# Adafruit_HUZZAH_ESP8266_Basic_Breakout.net
KiCad netlist of a schematic drawn in EAGLE
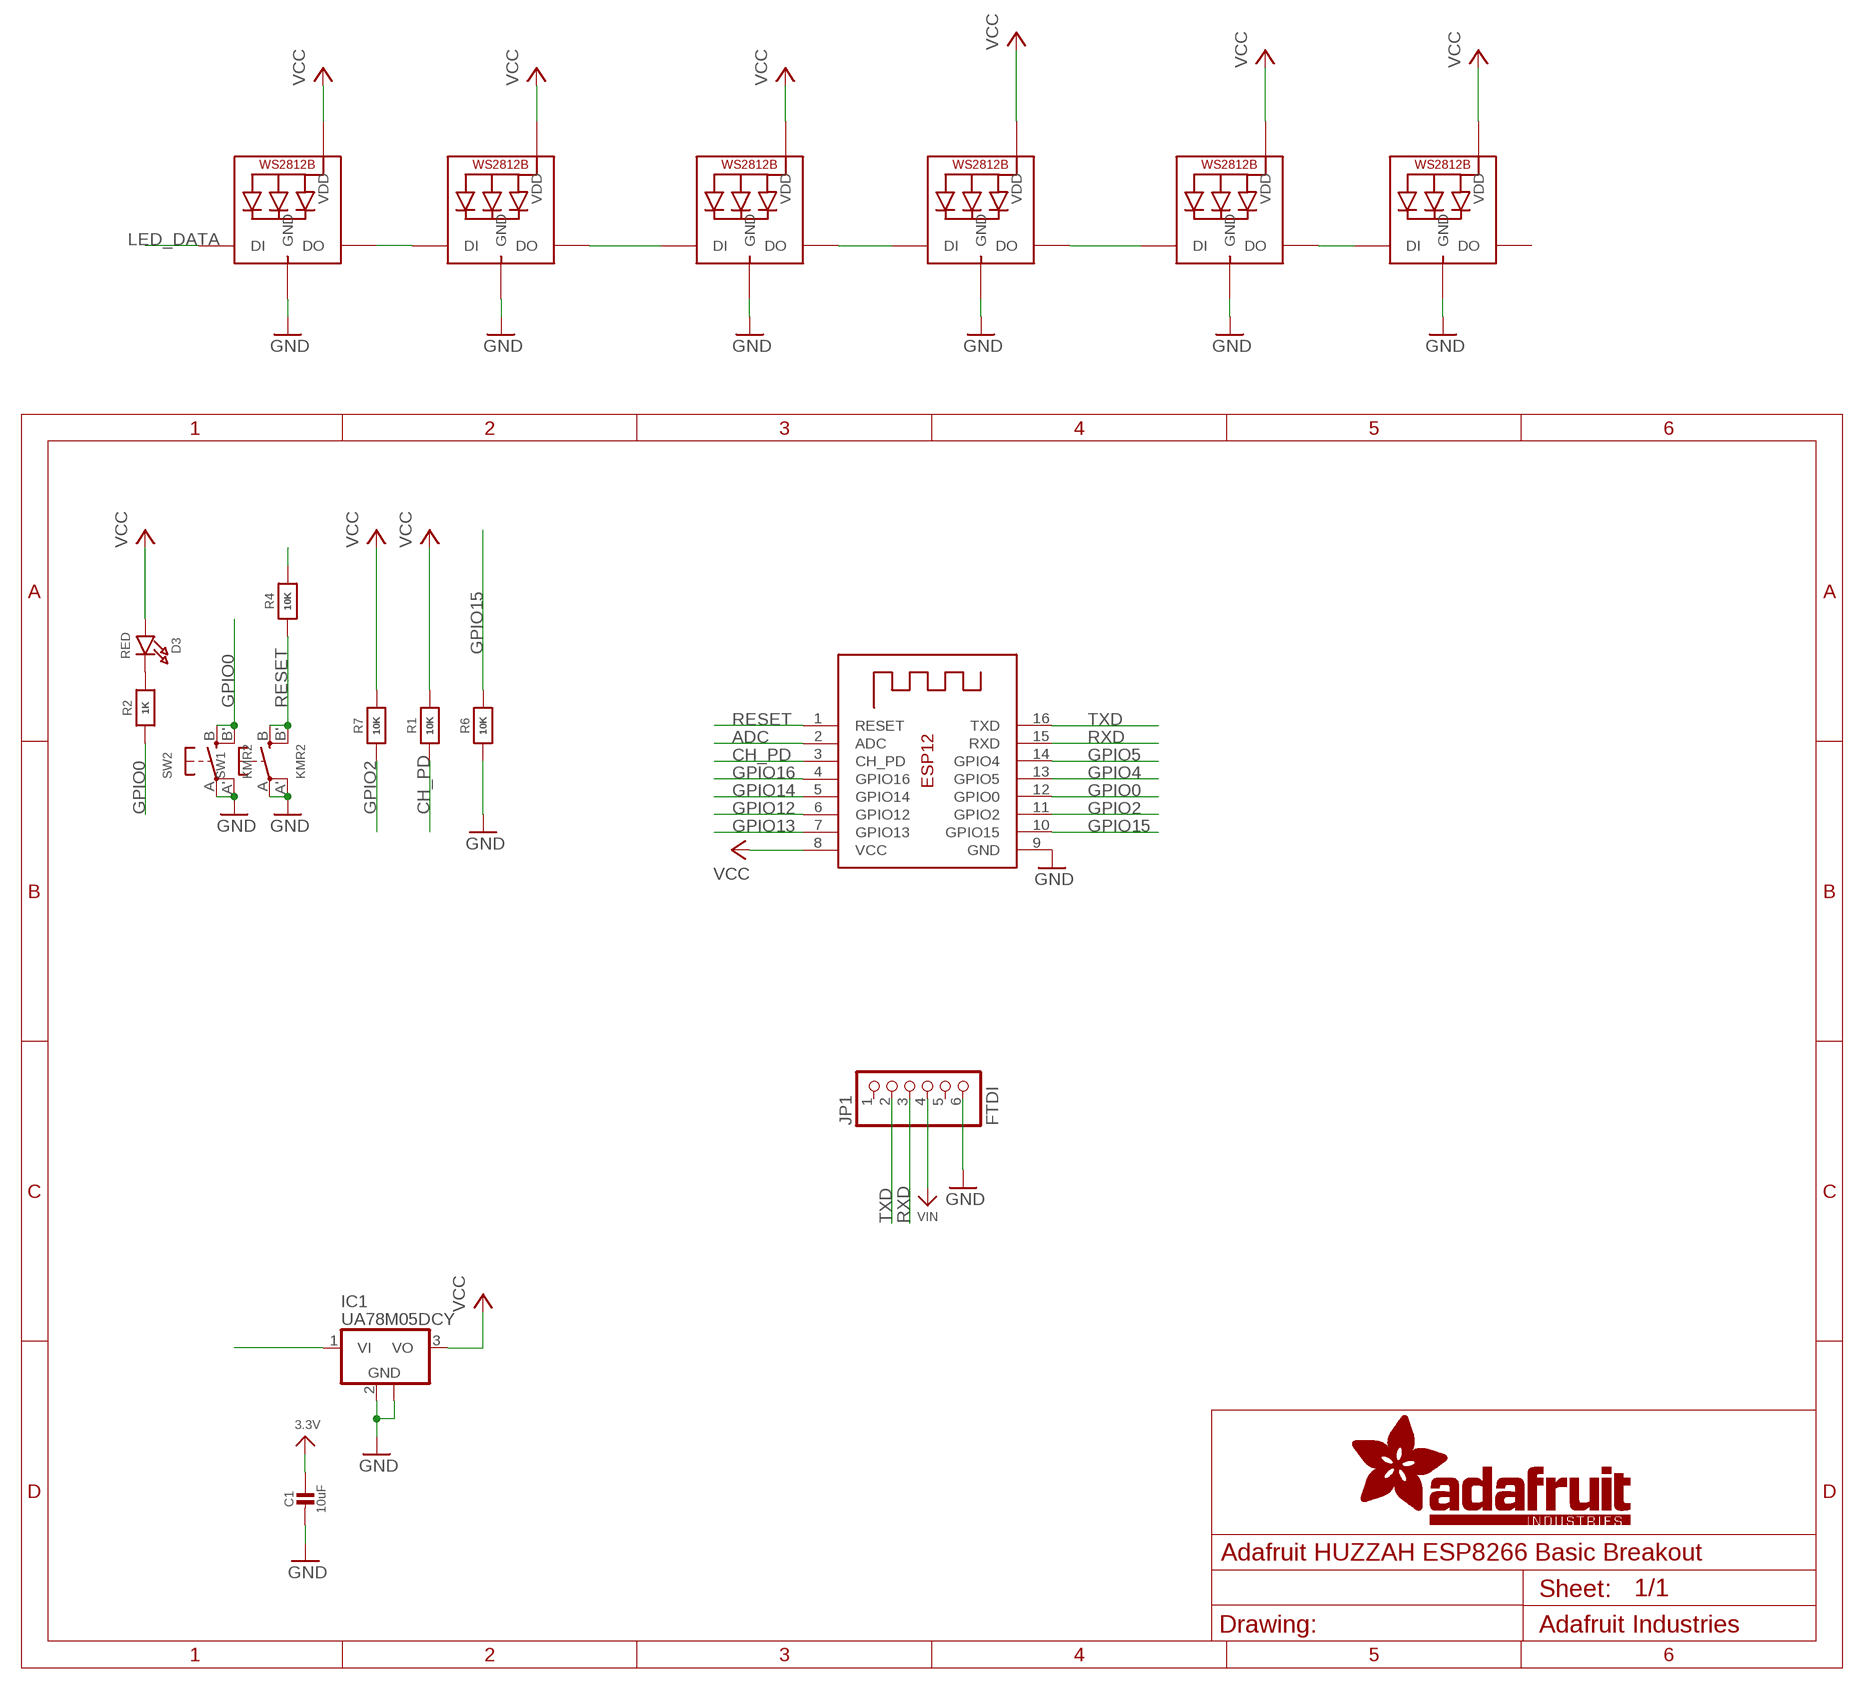
[diagram p0: schematic, sheet 1]

(export (version "E")
  (design (tool "Eeschema 10.0.6"))
  (components
    (comp (ref "C1")
      (value "10uF")
      (footprint "eagle-import:0805-NO")
      (libsource (lib "eagle-import") (part "CAP_CERAMIC0805-NOOUTLINE"))
    )
    (comp (ref "D3")
      (value "RED")
      (footprint "eagle-import:CHIPLED_0805_NOOUTLINE")
      (libsource (lib "eagle-import") (part "LED0805_NOOUTLINE"))
    )
    (comp (ref "IC1")
      (value "UA78M05DCY")
      (footprint "eagle-import:SOT223")
      (libsource (lib "eagle-import") (part "UA78MDCY05"))
    )
    (comp (ref "JP1")
      (value "FTDI")
      (footprint "eagle-import:1X06_ROUND_70")
      (libsource (lib "eagle-import") (part "HEADER-1X670MIL"))
    )
    (comp (ref "LED1")
      (value "WS2812B5050")
      (footprint "eagle-import:WS2812B")
      (libsource (lib "eagle-import") (part "WS2812B5050"))
    )
    (comp (ref "LED2")
      (value "WS2812B5050")
      (footprint "eagle-import:WS2812B")
      (libsource (lib "eagle-import") (part "WS2812B5050"))
    )
    (comp (ref "LED3")
      (value "WS2812B5050")
      (footprint "eagle-import:WS2812B")
      (libsource (lib "eagle-import") (part "WS2812B5050"))
    )
    (comp (ref "LED4")
      (value "WS2812B5050")
      (footprint "eagle-import:WS2812B")
      (libsource (lib "eagle-import") (part "WS2812B5050"))
    )
    (comp (ref "LED5")
      (value "WS2812B5050")
      (footprint "eagle-import:WS2812B")
      (libsource (lib "eagle-import") (part "WS2812B5050"))
    )
    (comp (ref "LED6")
      (value "WS2812B5050")
      (footprint "eagle-import:WS2812B")
      (libsource (lib "eagle-import") (part "WS2812B5050"))
    )
    (comp (ref "R1")
      (value "10K")
      (footprint "eagle-import:0805-NO")
      (libsource (lib "eagle-import") (part "RESISTOR0805_NOOUTLINE"))
    )
    (comp (ref "R2")
      (value "1K")
      (footprint "eagle-import:0805-NO")
      (libsource (lib "eagle-import") (part "RESISTOR0805_NOOUTLINE"))
    )
    (comp (ref "R4")
      (value "10K")
      (footprint "eagle-import:0805-NO")
      (libsource (lib "eagle-import") (part "RESISTOR0805_NOOUTLINE"))
    )
    (comp (ref "R6")
      (value "10K")
      (footprint "eagle-import:0805-NO")
      (libsource (lib "eagle-import") (part "RESISTOR0805_NOOUTLINE"))
    )
    (comp (ref "R7")
      (value "10K")
      (footprint "eagle-import:0805-NO")
      (libsource (lib "eagle-import") (part "RESISTOR0805_NOOUTLINE"))
    )
    (comp (ref "SW1")
      (value "KMR2")
      (footprint "eagle-import:BTN_KMR2_4.6X2.8")
      (libsource (lib "eagle-import") (part "SWITCH_TACT_SMT4.6X2.8"))
    )
    (comp (ref "SW2")
      (value "KMR2")
      (footprint "eagle-import:BTN_KMR2_4.6X2.8")
      (libsource (lib "eagle-import") (part "SWITCH_TACT_SMT4.6X2.8"))
    )
    (comp (ref "X1")
      (value "ESP-12")
      (footprint "eagle-import:ESP-12")
      (libsource (lib "eagle-import") (part "ESP-12"))
    )
  )
  (nets
    (net (code "1") (name "/ADC") (class "Default")
      (node (ref "X1") (pin "2") (pinfunction "ADC_2") (pintype "passive"))
    )
    (net (code "2") (name "/CH_PD") (class "Default")
      (node (ref "R1") (pin "1") (pinfunction "1_1") (pintype "passive"))
      (node (ref "X1") (pin "3") (pinfunction "CH_PD_3") (pintype "input"))
    )
    (net (code "3") (name "/GPIO0") (class "Default")
      (node (ref "R2") (pin "1") (pinfunction "1_1") (pintype "passive"))
      (node (ref "SW2") (pin "B") (pinfunction "S_B") (pintype "passive"))
      (node (ref "SW2") (pin "B'") (pinfunction "S1_B'") (pintype "passive"))
      (node (ref "X1") (pin "12") (pinfunction "GPIO0_12") (pintype "bidirectional"))
    )
    (net (code "4") (name "/GPIO2") (class "Default")
      (node (ref "R7") (pin "1") (pinfunction "1_1") (pintype "passive"))
      (node (ref "X1") (pin "11") (pinfunction "GPIO2_11") (pintype "bidirectional"))
    )
    (net (code "5") (name "/GPIO4") (class "Default")
      (node (ref "X1") (pin "13") (pinfunction "GPIO5_13") (pintype "bidirectional"))
    )
    (net (code "6") (name "/GPIO5") (class "Default")
      (node (ref "X1") (pin "14") (pinfunction "GPIO4_14") (pintype "bidirectional"))
    )
    (net (code "7") (name "/GPIO12") (class "Default")
      (node (ref "X1") (pin "6") (pinfunction "GPIO12_6") (pintype "bidirectional"))
    )
    (net (code "8") (name "/GPIO13") (class "Default")
      (node (ref "X1") (pin "7") (pinfunction "GPIO13_7") (pintype "bidirectional"))
    )
    (net (code "9") (name "/GPIO14") (class "Default")
      (node (ref "X1") (pin "5") (pinfunction "GPIO14_5") (pintype "bidirectional"))
    )
    (net (code "10") (name "/GPIO15") (class "Default")
      (node (ref "R6") (pin "2") (pinfunction "2_2") (pintype "passive"))
      (node (ref "X1") (pin "10") (pinfunction "GPIO15_10") (pintype "bidirectional"))
    )
    (net (code "11") (name "/GPIO16") (class "Default")
      (node (ref "X1") (pin "4") (pinfunction "GPIO16_4") (pintype "bidirectional"))
    )
    (net (code "12") (name "/LED_DATA") (class "Default")
      (node (ref "LED1") (pin "4-DIN") (pinfunction "DI_4-DIN") (pintype "input"))
    )
    (net (code "13") (name "/RESET") (class "Default")
      (node (ref "R4") (pin "1") (pinfunction "1_1") (pintype "passive"))
      (node (ref "SW1") (pin "B") (pinfunction "S_B") (pintype "passive"))
      (node (ref "SW1") (pin "B'") (pinfunction "S1_B'") (pintype "passive"))
      (node (ref "X1") (pin "1") (pinfunction "RESET_1") (pintype "input"))
    )
    (net (code "14") (name "/RXD") (class "Default")
      (node (ref "JP1") (pin "3") (pinfunction "3_3") (pintype "passive"))
      (node (ref "X1") (pin "15") (pinfunction "RXD_15") (pintype "input"))
    )
    (net (code "15") (name "/TXD") (class "Default")
      (node (ref "JP1") (pin "2") (pinfunction "2_2") (pintype "passive"))
      (node (ref "X1") (pin "16") (pinfunction "TXD_16") (pintype "output"))
    )
    (net (code "16") (name "3.3V") (class "Default")
      (node (ref "C1") (pin "1") (pinfunction "1_1") (pintype "passive"))
    )
    (net (code "17") (name "GND") (class "Default")
      (node (ref "C1") (pin "2") (pinfunction "2_2") (pintype "passive"))
      (node (ref "IC1") (pin "2") (pinfunction "GND_2") (pintype "passive"))
      (node (ref "IC1") (pin "4") (pinfunction "GND_4") (pintype "passive"))
      (node (ref "JP1") (pin "6") (pinfunction "6_6") (pintype "passive"))
      (node (ref "LED1") (pin "3-GND") (pinfunction "GND_3-GND") (pintype "power_in"))
      (node (ref "LED2") (pin "3-GND") (pinfunction "GND_3-GND") (pintype "power_in"))
      (node (ref "LED3") (pin "3-GND") (pinfunction "GND_3-GND") (pintype "power_in"))
      (node (ref "LED4") (pin "3-GND") (pinfunction "GND_3-GND") (pintype "power_in"))
      (node (ref "LED5") (pin "3-GND") (pinfunction "GND_3-GND") (pintype "power_in"))
      (node (ref "LED6") (pin "3-GND") (pinfunction "GND_3-GND") (pintype "power_in"))
      (node (ref "R6") (pin "1") (pinfunction "1_1") (pintype "passive"))
      (node (ref "SW1") (pin "A") (pinfunction "P_A") (pintype "passive"))
      (node (ref "SW1") (pin "A'") (pinfunction "P1_A'") (pintype "passive"))
      (node (ref "SW2") (pin "A") (pinfunction "P_A") (pintype "passive"))
      (node (ref "SW2") (pin "A'") (pinfunction "P1_A'") (pintype "passive"))
      (node (ref "X1") (pin "9") (pinfunction "GND_9") (pintype "power_in"))
    )
    (net (code "18") (name "Net-(D3-PadC)") (class "Default")
      (node (ref "D3") (pin "C") (pinfunction "C_C") (pintype "passive"))
      (node (ref "R2") (pin "2") (pinfunction "2_2") (pintype "passive"))
    )
    (net (code "19") (name "Net-(LED1-DO)") (class "Default")
      (node (ref "LED1") (pin "2-DOUT") (pinfunction "DO_2-DOUT") (pintype "output"))
      (node (ref "LED2") (pin "4-DIN") (pinfunction "DI_4-DIN") (pintype "input"))
    )
    (net (code "20") (name "Net-(LED2-DO)") (class "Default")
      (node (ref "LED2") (pin "2-DOUT") (pinfunction "DO_2-DOUT") (pintype "output"))
      (node (ref "LED3") (pin "4-DIN") (pinfunction "DI_4-DIN") (pintype "input"))
    )
    (net (code "21") (name "Net-(LED3-DO)") (class "Default")
      (node (ref "LED3") (pin "2-DOUT") (pinfunction "DO_2-DOUT") (pintype "output"))
      (node (ref "LED4") (pin "4-DIN") (pinfunction "DI_4-DIN") (pintype "input"))
    )
    (net (code "22") (name "Net-(LED4-DO)") (class "Default")
      (node (ref "LED4") (pin "2-DOUT") (pinfunction "DO_2-DOUT") (pintype "output"))
      (node (ref "LED5") (pin "4-DIN") (pinfunction "DI_4-DIN") (pintype "input"))
    )
    (net (code "23") (name "Net-(LED5-DO)") (class "Default")
      (node (ref "LED5") (pin "2-DOUT") (pinfunction "DO_2-DOUT") (pintype "output"))
      (node (ref "LED6") (pin "4-DIN") (pinfunction "DI_4-DIN") (pintype "input"))
    )
    (net (code "24") (name "VCC") (class "Default")
      (node (ref "D3") (pin "A") (pinfunction "A_A") (pintype "passive"))
      (node (ref "IC1") (pin "3") (pinfunction "VO_3") (pintype "passive"))
      (node (ref "LED1") (pin "1-VDD") (pinfunction "VDD_1-VDD") (pintype "power_in"))
      (node (ref "LED2") (pin "1-VDD") (pinfunction "VDD_1-VDD") (pintype "power_in"))
      (node (ref "LED3") (pin "1-VDD") (pinfunction "VDD_1-VDD") (pintype "power_in"))
      (node (ref "LED4") (pin "1-VDD") (pinfunction "VDD_1-VDD") (pintype "power_in"))
      (node (ref "LED5") (pin "1-VDD") (pinfunction "VDD_1-VDD") (pintype "power_in"))
      (node (ref "LED6") (pin "1-VDD") (pinfunction "VDD_1-VDD") (pintype "power_in"))
      (node (ref "R1") (pin "2") (pinfunction "2_2") (pintype "passive"))
      (node (ref "R7") (pin "2") (pinfunction "2_2") (pintype "passive"))
      (node (ref "X1") (pin "8") (pinfunction "VCC_8") (pintype "power_in"))
    )
    (net (code "25") (name "VIN") (class "Default")
      (node (ref "JP1") (pin "4") (pinfunction "4_4") (pintype "passive"))
    )
    (net (code "26") (name "unconnected-(IC1-VI-Pad1)") (class "Default")
      (node (ref "IC1") (pin "1") (pinfunction "VI_1") (pintype "input"))
    )
    (net (code "27") (name "unconnected-(JP1-Pad1)") (class "Default")
      (node (ref "JP1") (pin "1") (pinfunction "1_1") (pintype "passive"))
    )
    (net (code "28") (name "unconnected-(JP1-Pad5)") (class "Default")
      (node (ref "JP1") (pin "5") (pinfunction "5_5") (pintype "passive"))
    )
    (net (code "29") (name "unconnected-(LED6-DO-Pad2-DOUT)") (class "Default")
      (node (ref "LED6") (pin "2-DOUT") (pinfunction "DO_2-DOUT") (pintype "output"))
    )
    (net (code "30") (name "unconnected-(R4-Pad2)") (class "Default")
      (node (ref "R4") (pin "2") (pinfunction "2_2") (pintype "passive"))
    )
  )
)
